# Sheet4550_1.net
KiCad netlist of a schematic drawn in Altium Designer
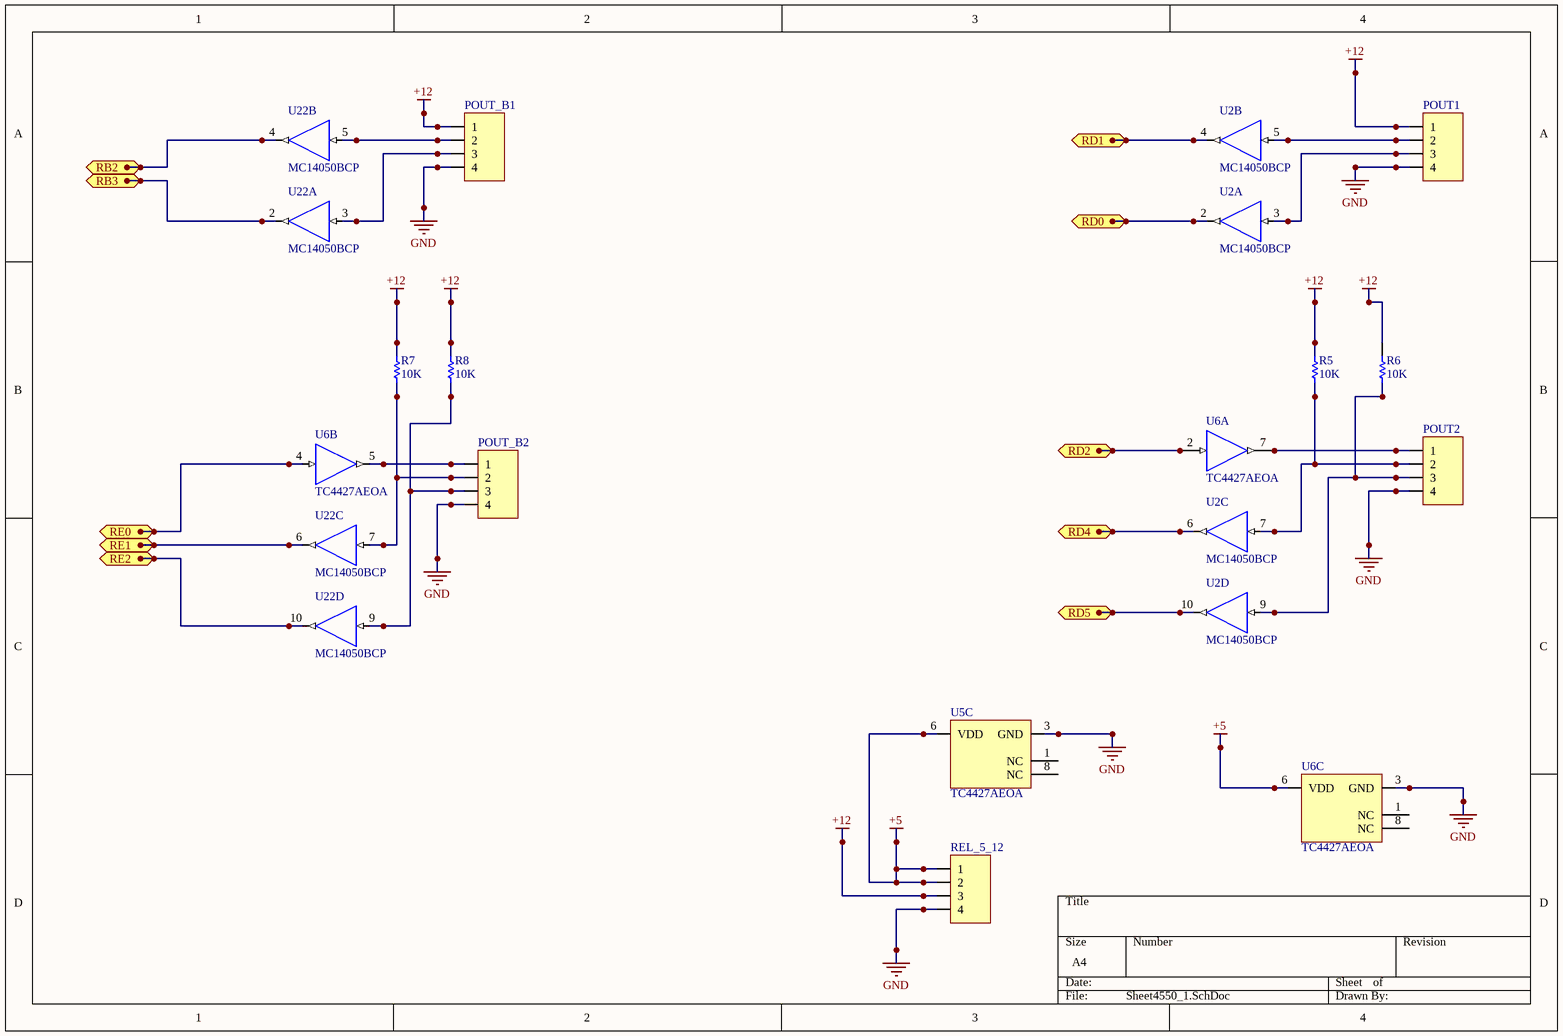
[diagram p0: Sheet4550_1.SchDoc]

(export (version "E")
  (design (tool "Eeschema 10.0.6"))
  (components
    (comp (ref "POUT1")
      (value "Big1")
      (footprint "BIG4")
      (description "Header, 4-Pin")
      (fields (field (name "PUBLISHER") "Altium Limited"))
      (libsource (lib "PCB_4550") (part "Header 4"))
    )
    (comp (ref "POUT2")
      (value "Big1")
      (footprint "BIG4")
      (description "Header, 4-Pin")
      (fields (field (name "PUBLISHER") "Altium Limited"))
      (libsource (lib "PCB_4550") (part "Header 4"))
    )
    (comp (ref "POUT_B1")
      (value "Big1")
      (footprint "BIG4")
      (description "Header, 4-Pin")
      (fields (field (name "PUBLISHER") "Altium Limited"))
      (libsource (lib "PCB_4550") (part "Header 4"))
    )
    (comp (ref "POUT_B2")
      (value "Big1")
      (footprint "BIG4")
      (description "Header, 4-Pin")
      (fields (field (name "PUBLISHER") "Altium Limited"))
      (libsource (lib "PCB_4550") (part "Header 4"))
    )
    (comp (ref "R5")
      (value "10K")
      (footprint "RESC3216L")
      (description "Semiconductor Resistor")
      (fields (field (name "PUBLISHER") "Altium Limited"))
      (libsource (lib "Miscellaneous Devices") (part "Res Semi"))
    )
    (comp (ref "R6")
      (value "10K")
      (footprint "RESC3216L")
      (description "Semiconductor Resistor")
      (fields (field (name "PUBLISHER") "Altium Limited"))
      (libsource (lib "Miscellaneous Devices") (part "Res Semi"))
    )
    (comp (ref "R7")
      (value "10K")
      (footprint "RESC3216L")
      (description "Semiconductor Resistor")
      (fields (field (name "PUBLISHER") "Altium Limited"))
      (libsource (lib "Miscellaneous Devices") (part "Res Semi"))
    )
    (comp (ref "R8")
      (value "10K")
      (footprint "RESC3216L")
      (description "Semiconductor Resistor")
      (fields (field (name "PUBLISHER") "Altium Limited"))
      (libsource (lib "Miscellaneous Devices") (part "Res Semi"))
    )
    (comp (ref "REL_5_12")
      (value "Header 4")
      (footprint "HDR1X4")
      (description "Header, 4-Pin")
      (fields (field (name "PUBLISHER") "Altium Limited"))
      (libsource (lib "Miscellaneous Connectors") (part "Header 4"))
    )
    (comp (ref "U2")
      (value "MC14050BCP")
      (footprint "648-08")
      (description "Hex Non-Inverting Buffer")
      (fields (field (name "PUBLISHER") "Altium Limited"))
      (libsource (lib "ON Semi Logic Buffer Line Driver") (part "MC14050BCP"))
    )
    (comp (ref "U5")
      (value "TC4427AEOA")
      (footprint "SOIC-OA8_N")
      (description "1.5A Dual High-Speed Power MOSFET Driver, Non-Inverting, Industrial Temperature")
      (fields (field (name "PUBLISHER") "Altium Limited"))
      (libsource (lib "Microchip Power Mgt MOSFET Driver") (part "TC4427AEOA"))
    )
    (comp (ref "U6")
      (value "TC4427AEOA")
      (footprint "SOIC-OA8_N")
      (description "1.5A Dual High-Speed Power MOSFET Driver, Non-Inverting, Industrial Temperature")
      (fields (field (name "PUBLISHER") "Altium Limited"))
      (libsource (lib "Microchip Power Mgt MOSFET Driver") (part "TC4427AEOA"))
    )
    (comp (ref "U22")
      (value "MC14050BCP")
      (footprint "648-08")
      (description "Hex Non-Inverting Buffer")
      (fields (field (name "PUBLISHER") "Altium Limited"))
      (libsource (lib "ON Semi Logic Buffer Line Driver") (part "MC14050BCP"))
    )
  )
  (nets
    (net (code "1") (name "+5") (class "Default")
      (node (ref "REL_5_12") (pin "1") (pinfunction "1_1") (pintype "passive"))
      (node (ref "REL_5_12") (pin "2") (pinfunction "2_2") (pintype "passive"))
      (node (ref "U5") (pin "6") (pinfunction "VDD_6") (pintype "power_in"))
      (node (ref "U6") (pin "6") (pinfunction "VDD_6") (pintype "power_in"))
    )
    (net (code "2") (name "+12") (class "Default")
      (node (ref "POUT1") (pin "1") (pinfunction "1_1") (pintype "passive"))
      (node (ref "POUT_B1") (pin "1") (pinfunction "1_1") (pintype "passive"))
      (node (ref "R5") (pin "2") (pinfunction "2_2") (pintype "passive"))
      (node (ref "R6") (pin "2") (pinfunction "2_2") (pintype "passive"))
      (node (ref "R7") (pin "2") (pinfunction "2_2") (pintype "passive"))
      (node (ref "R8") (pin "2") (pinfunction "2_2") (pintype "passive"))
      (node (ref "REL_5_12") (pin "3") (pinfunction "3_3") (pintype "passive"))
    )
    (net (code "3") (name "/RB2") (class "Default")
      (node (ref "U22") (pin "4") (pinfunction "OUT_4") (pintype "output"))
    )
    (net (code "4") (name "/RB3") (class "Default")
      (node (ref "U22") (pin "2") (pinfunction "OUT_2") (pintype "output"))
    )
    (net (code "5") (name "/RD0") (class "Default")
      (node (ref "U2") (pin "2") (pinfunction "OUT_2") (pintype "output"))
    )
    (net (code "6") (name "/RD1") (class "Default")
      (node (ref "U2") (pin "4") (pinfunction "OUT_4") (pintype "output"))
    )
    (net (code "7") (name "/RD2") (class "Default")
      (node (ref "U6") (pin "2") (pinfunction "INA_2") (pintype "input"))
    )
    (net (code "8") (name "/RD4") (class "Default")
      (node (ref "U2") (pin "6") (pinfunction "OUT_6") (pintype "output"))
    )
    (net (code "9") (name "/RD5") (class "Default")
      (node (ref "U2") (pin "10") (pinfunction "OUT_10") (pintype "output"))
    )
    (net (code "10") (name "/RE0") (class "Default")
      (node (ref "U6") (pin "4") (pinfunction "INB_4") (pintype "input"))
    )
    (net (code "11") (name "/RE1") (class "Default")
      (node (ref "U22") (pin "6") (pinfunction "OUT_6") (pintype "output"))
    )
    (net (code "12") (name "/RE2") (class "Default")
      (node (ref "U22") (pin "10") (pinfunction "OUT_10") (pintype "output"))
    )
    (net (code "13") (name "GND") (class "Default")
      (node (ref "POUT1") (pin "4") (pinfunction "4_4") (pintype "passive"))
      (node (ref "POUT2") (pin "4") (pinfunction "4_4") (pintype "passive"))
      (node (ref "POUT_B1") (pin "4") (pinfunction "4_4") (pintype "passive"))
      (node (ref "POUT_B2") (pin "4") (pinfunction "4_4") (pintype "passive"))
      (node (ref "REL_5_12") (pin "4") (pinfunction "4_4") (pintype "passive"))
      (node (ref "U2") (pin "8") (pinfunction "GND_8") (pintype "power_in"))
      (node (ref "U22") (pin "8") (pinfunction "GND_8") (pintype "power_in"))
      (node (ref "U5") (pin "3") (pinfunction "GND_3") (pintype "power_in"))
      (node (ref "U6") (pin "3") (pinfunction "GND_3") (pintype "power_in"))
    )
    (net (code "14") (name "Net-(U2A-IN)") (class "Default")
      (node (ref "POUT1") (pin "3") (pinfunction "3_3") (pintype "passive"))
      (node (ref "U2") (pin "3") (pinfunction "IN_3") (pintype "input"))
    )
    (net (code "15") (name "Net-(U2B-IN)") (class "Default")
      (node (ref "POUT1") (pin "2") (pinfunction "2_2") (pintype "passive"))
      (node (ref "U2") (pin "5") (pinfunction "IN_5") (pintype "input"))
    )
    (net (code "16") (name "Net-(U2C-IN)") (class "Default")
      (node (ref "POUT2") (pin "2") (pinfunction "2_2") (pintype "passive"))
      (node (ref "R5") (pin "1") (pinfunction "1_1") (pintype "passive"))
      (node (ref "U2") (pin "7") (pinfunction "IN_7") (pintype "input"))
    )
    (net (code "17") (name "Net-(U2D-IN)") (class "Default")
      (node (ref "POUT2") (pin "3") (pinfunction "3_3") (pintype "passive"))
      (node (ref "R6") (pin "1") (pinfunction "1_1") (pintype "passive"))
      (node (ref "U2") (pin "9") (pinfunction "IN_9") (pintype "input"))
    )
    (net (code "18") (name "Net-(U6A-OUTA)") (class "Default")
      (node (ref "POUT2") (pin "1") (pinfunction "1_1") (pintype "passive"))
      (node (ref "U6") (pin "7") (pinfunction "OUTA_7") (pintype "output"))
    )
    (net (code "19") (name "Net-(U6B-OUTB)") (class "Default")
      (node (ref "POUT_B2") (pin "1") (pinfunction "1_1") (pintype "passive"))
      (node (ref "U6") (pin "5") (pinfunction "OUTB_5") (pintype "output"))
    )
    (net (code "20") (name "Net-(U22A-IN)") (class "Default")
      (node (ref "POUT_B1") (pin "3") (pinfunction "3_3") (pintype "passive"))
      (node (ref "U22") (pin "3") (pinfunction "IN_3") (pintype "input"))
    )
    (net (code "21") (name "Net-(U22B-IN)") (class "Default")
      (node (ref "POUT_B1") (pin "2") (pinfunction "2_2") (pintype "passive"))
      (node (ref "U22") (pin "5") (pinfunction "IN_5") (pintype "input"))
    )
    (net (code "22") (name "Net-(U22C-IN)") (class "Default")
      (node (ref "POUT_B2") (pin "2") (pinfunction "2_2") (pintype "passive"))
      (node (ref "R7") (pin "1") (pinfunction "1_1") (pintype "passive"))
      (node (ref "U22") (pin "7") (pinfunction "IN_7") (pintype "input"))
    )
    (net (code "23") (name "Net-(U22D-IN)") (class "Default")
      (node (ref "POUT_B2") (pin "3") (pinfunction "3_3") (pintype "passive"))
      (node (ref "R8") (pin "1") (pinfunction "1_1") (pintype "passive"))
      (node (ref "U22") (pin "9") (pinfunction "IN_9") (pintype "input"))
    )
    (net (code "24") (name "VDD") (class "Default")
      (node (ref "U2") (pin "1") (pinfunction "VDD_1") (pintype "power_in"))
      (node (ref "U22") (pin "1") (pinfunction "VDD_1") (pintype "power_in"))
    )
    (net (code "25") (name "unconnected-(U5C-NC-Pad1)") (class "Default")
      (node (ref "U5") (pin "1") (pinfunction "NC_1") (pintype "passive"))
    )
    (net (code "26") (name "unconnected-(U5C-NC-Pad8)") (class "Default")
      (node (ref "U5") (pin "8") (pinfunction "NC_8") (pintype "passive"))
    )
    (net (code "27") (name "unconnected-(U6C-NC-Pad1)") (class "Default")
      (node (ref "U6") (pin "1") (pinfunction "NC_1") (pintype "passive"))
    )
    (net (code "28") (name "unconnected-(U6C-NC-Pad8)") (class "Default")
      (node (ref "U6") (pin "8") (pinfunction "NC_8") (pintype "passive"))
    )
  )
)
